# CW308T_AVR_MICRO.net
KiCad netlist of a schematic drawn in Altium Designer
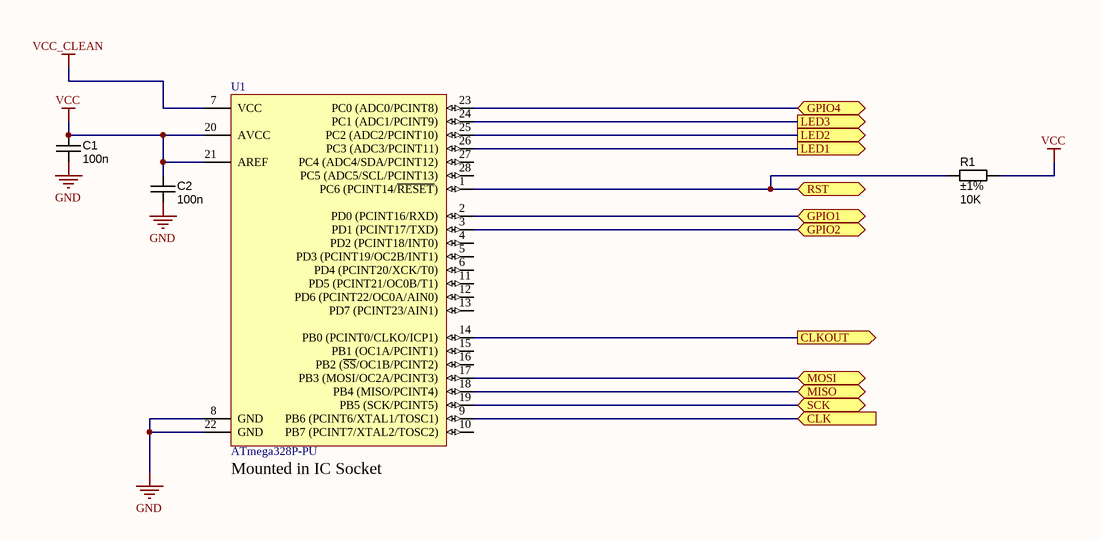
[diagram p0: CW308T_AVR_MICRO.SchDoc]

(export (version "E")
  (design (tool "Eeschema 10.0.6"))
  (components
    (comp (ref "C1")
      (value "100n")
      (footprint "CAPC1608X90N")
      (description "Capacitor SMD Cer 100nF 10% 50V X7R 0603")
      (fields (field (name "TOLERANCE") "±10%") (field (name "Comment") "approved sub OK"))
      (libsource (lib "PBL - Capacitors") (part "CAPC_100n_0603_X7R_50V_10%"))
    )
    (comp (ref "C2")
      (value "100n")
      (footprint "CAPC1608X90N")
      (description "Capacitor SMD Cer 100nF 10% 50V X7R 0603")
      (fields (field (name "TOLERANCE") "±10%") (field (name "Comment") "approved sub OK"))
      (libsource (lib "PBL - Capacitors") (part "CAPC_100n_0603_X7R_50V_10%"))
    )
    (comp (ref "R1")
      (value "10K")
      (footprint "RESC1608X55N")
      (description "Resistor SMD chip 10k Ohm 0.1W 1% 0603")
      (fields (field (name "TOLERANCE") "±1%") (field (name "Comment") "Thick Film"))
      (libsource (lib "PBL - Resistors") (part "RES_10K_0603_1%"))
    )
    (comp (ref "U1")
      (value "ATmega328P-PU")
      (footprint "28P3")
      (libsource (lib "Altium Content Vault") (part "MC-8B-ATM48-IL28"))
    )
  )
  (nets
    (net (code "1") (name "/CLK") (class "Default")
      (node (ref "U1") (pin "9") (pinfunction "PB6_(PCINT6/XTAL1/TOSC1)_9") (pintype "bidirectional"))
    )
    (net (code "2") (name "/CLKOUT") (class "Default")
      (node (ref "U1") (pin "14") (pinfunction "PB0_(PCINT0/CLKO/ICP1)_14") (pintype "bidirectional"))
    )
    (net (code "3") (name "/GPIO1") (class "Default")
      (node (ref "U1") (pin "2") (pinfunction "PD0_(PCINT16/RXD)_2") (pintype "bidirectional"))
    )
    (net (code "4") (name "/GPIO2") (class "Default")
      (node (ref "U1") (pin "3") (pinfunction "PD1_(PCINT17/TXD)_3") (pintype "bidirectional"))
    )
    (net (code "5") (name "/GPIO4") (class "Default")
      (node (ref "U1") (pin "23") (pinfunction "PC0_(ADC0/PCINT8)_23") (pintype "bidirectional"))
    )
    (net (code "6") (name "/LED1") (class "Default")
      (node (ref "U1") (pin "26") (pinfunction "PC3_(ADC3/PCINT11)_26") (pintype "bidirectional"))
    )
    (net (code "7") (name "/LED2") (class "Default")
      (node (ref "U1") (pin "25") (pinfunction "PC2_(ADC2/PCINT10)_25") (pintype "bidirectional"))
    )
    (net (code "8") (name "/LED3") (class "Default")
      (node (ref "U1") (pin "24") (pinfunction "PC1_(ADC1/PCINT9)_24") (pintype "bidirectional"))
    )
    (net (code "9") (name "/MISO") (class "Default")
      (node (ref "U1") (pin "18") (pinfunction "PB4_(MISO/PCINT4)_18") (pintype "bidirectional"))
    )
    (net (code "10") (name "/MOSI") (class "Default")
      (node (ref "U1") (pin "17") (pinfunction "PB3_(MOSI/OC2A/PCINT3)_17") (pintype "bidirectional"))
    )
    (net (code "11") (name "/RST") (class "Default")
      (node (ref "R1") (pin "2") (pinfunction "2_2") (pintype "passive"))
      (node (ref "U1") (pin "1") (pinfunction "PC6_(PCINT14/~{RESET})_1") (pintype "bidirectional"))
    )
    (net (code "12") (name "/SCK") (class "Default")
      (node (ref "U1") (pin "19") (pinfunction "PB5_(SCK/PCINT5)_19") (pintype "bidirectional"))
    )
    (net (code "13") (name "GND") (class "Default")
      (node (ref "C1") (pin "2") (pintype "passive"))
      (node (ref "C2") (pin "2") (pintype "passive"))
      (node (ref "U1") (pin "22") (pinfunction "GND_22") (pintype "power_in"))
      (node (ref "U1") (pin "8") (pinfunction "GND_8") (pintype "power_in"))
    )
    (net (code "14") (name "VCC") (class "Default")
      (node (ref "C1") (pin "1") (pintype "passive"))
      (node (ref "C2") (pin "1") (pintype "passive"))
      (node (ref "R1") (pin "1") (pinfunction "1_1") (pintype "passive"))
      (node (ref "U1") (pin "20") (pinfunction "AVCC_20") (pintype "power_in"))
      (node (ref "U1") (pin "21") (pinfunction "AREF_21") (pintype "power_in"))
    )
    (net (code "15") (name "VCC_CLEAN") (class "Default")
      (node (ref "U1") (pin "7") (pinfunction "VCC_7") (pintype "power_in"))
    )
    (net (code "16") (name "unconnected-(U1-PB1_(OC1A{slash}PCINT1)-Pad15)") (class "Default")
      (node (ref "U1") (pin "15") (pinfunction "PB1_(OC1A/PCINT1)_15") (pintype "bidirectional"))
    )
    (net (code "17") (name "unconnected-(U1-PB2_(~{SS}{slash}OC1B{slash}PCINT2)-Pad16)") (class "Default")
      (node (ref "U1") (pin "16") (pinfunction "PB2_(~{SS}/OC1B/PCINT2)_16") (pintype "bidirectional"))
    )
    (net (code "18") (name "unconnected-(U1-PB7_(PCINT7{slash}XTAL2{slash}TOSC2)-Pad10)") (class "Default")
      (node (ref "U1") (pin "10") (pinfunction "PB7_(PCINT7/XTAL2/TOSC2)_10") (pintype "bidirectional"))
    )
    (net (code "19") (name "unconnected-(U1-PC4_(ADC4{slash}SDA{slash}PCINT12)-Pad27)") (class "Default")
      (node (ref "U1") (pin "27") (pinfunction "PC4_(ADC4/SDA/PCINT12)_27") (pintype "bidirectional"))
    )
    (net (code "20") (name "unconnected-(U1-PC5_(ADC5{slash}SCL{slash}PCINT13)-Pad28)") (class "Default")
      (node (ref "U1") (pin "28") (pinfunction "PC5_(ADC5/SCL/PCINT13)_28") (pintype "bidirectional"))
    )
    (net (code "21") (name "unconnected-(U1-PD2_(PCINT18{slash}INT0)-Pad4)") (class "Default")
      (node (ref "U1") (pin "4") (pinfunction "PD2_(PCINT18/INT0)_4") (pintype "bidirectional"))
    )
    (net (code "22") (name "unconnected-(U1-PD3_(PCINT19{slash}OC2B{slash}INT1)-Pad5)") (class "Default")
      (node (ref "U1") (pin "5") (pinfunction "PD3_(PCINT19/OC2B/INT1)_5") (pintype "bidirectional"))
    )
    (net (code "23") (name "unconnected-(U1-PD4_(PCINT20{slash}XCK{slash}T0)-Pad6)") (class "Default")
      (node (ref "U1") (pin "6") (pinfunction "PD4_(PCINT20/XCK/T0)_6") (pintype "bidirectional"))
    )
    (net (code "24") (name "unconnected-(U1-PD5_(PCINT21{slash}OC0B{slash}T1)-Pad11)") (class "Default")
      (node (ref "U1") (pin "11") (pinfunction "PD5_(PCINT21/OC0B/T1)_11") (pintype "bidirectional"))
    )
    (net (code "25") (name "unconnected-(U1-PD6_(PCINT22{slash}OC0A{slash}AIN0)-Pad12)") (class "Default")
      (node (ref "U1") (pin "12") (pinfunction "PD6_(PCINT22/OC0A/AIN0)_12") (pintype "bidirectional"))
    )
    (net (code "26") (name "unconnected-(U1-PD7_(PCINT23{slash}AIN1)-Pad13)") (class "Default")
      (node (ref "U1") (pin "13") (pinfunction "PD7_(PCINT23/AIN1)_13") (pintype "bidirectional"))
    )
  )
)
